# CH32X035C-R0.net
KiCad netlist of a schematic drawn in Altium Designer
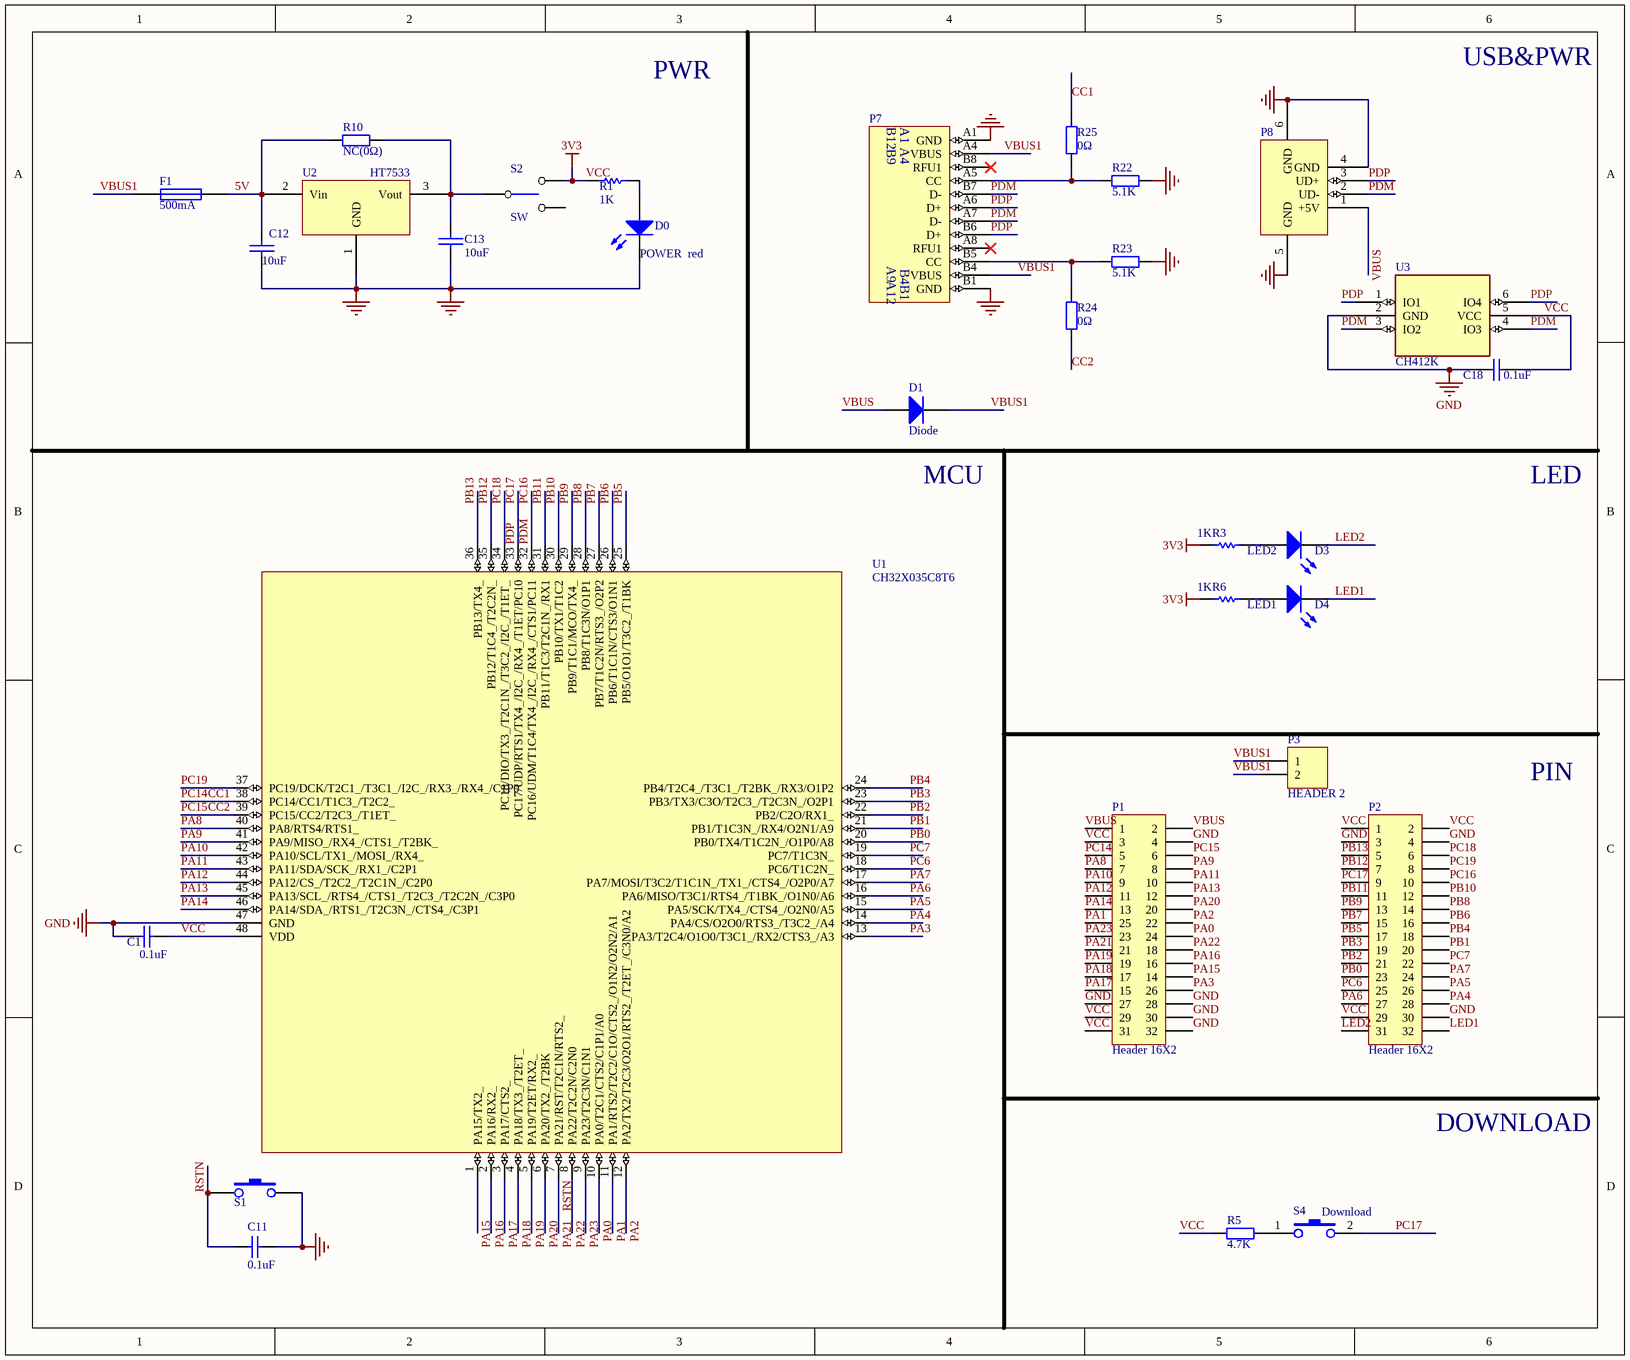
[diagram p0: CH32X035C-R0.SchDoc]

(export (version "E")
  (design (tool "Eeschema 10.0.6"))
  (components
    (comp (ref "C1")
      (value "0.1uF")
      (footprint "0603_C")
      (description "Capacitor")
      (libsource (lib "Miscellaneous Devices") (part "Cap"))
    )
    (comp (ref "C11")
      (value "0.1uF")
      (footprint "0603_C")
      (description "Capacitor")
      (libsource (lib "*") (part "Cap"))
    )
    (comp (ref "C12")
      (value "10uF")
      (footprint "0603_C")
      (description "Capacitor")
      (libsource (lib "*") (part "CAP"))
    )
    (comp (ref "C13")
      (value "10uF")
      (footprint "0603_C")
      (description "Capacitor")
      (libsource (lib "*") (part "CAP"))
    )
    (comp (ref "C18")
      (value "0.1uF")
      (footprint "0603_C")
      (description "Capacitor")
      (libsource (lib "Miscellaneous Devices") (part "Cap"))
    )
    (comp (ref "D0")
      (value "POWER  red")
      (footprint "0603+")
      (description "Typical INFRARED GaAs LED")
      (fields (field (name "PUBLISHER") "Altium Limited"))
      (libsource (lib "*") (part "LED0"))
    )
    (comp (ref "D1")
      (value "Diode")
      (footprint "SOD-123")
      (description "Default Diode")
      (fields (field (name "PUBLISHER") "Altium Limited"))
      (libsource (lib "Miscellaneous Devices") (part "Diode"))
    )
    (comp (ref "D3")
      (value "LED2")
      (footprint "0603+")
      (description "Typical INFRARED GaAs LED")
      (fields (field (name "PUBLISHER") "Altium Limited"))
      (libsource (lib "*") (part "LED0"))
    )
    (comp (ref "D4")
      (value "LED1")
      (footprint "0603+")
      (description "Typical INFRARED GaAs LED")
      (fields (field (name "PUBLISHER") "Altium Limited"))
      (libsource (lib "*") (part "LED0"))
    )
    (comp (ref "F1")
      (value "500mA")
      (footprint "0603")
      (description "Fuse")
      (libsource (lib "*") (part "FUSE1"))
    )
    (comp (ref "P1")
      (value "Header 16X2")
      (footprint "IDC32-2.54mm")
      (description "Header, 16-Pin, Dual row")
      (fields (field (name "PUBLISHER") "Altium Limited"))
      (libsource (lib "Miscellaneous Connectors") (part "Header 16X2"))
    )
    (comp (ref "P2")
      (value "Header 16X2")
      (footprint "IDC32-2.54mm")
      (description "Header, 16-Pin, Dual row")
      (fields (field (name "PUBLISHER") "Altium Limited"))
      (libsource (lib "") (part "Header 16X2_1"))
    )
    (comp (ref "P3")
      (value "HEADER 2")
      (footprint "SIP2-2.54mm")
      (description "Header, 2-Pin")
      (libsource (lib "wch_sch_others") (part "HEADER 2"))
    )
    (comp (ref "P7")
      (value "TYPE-C")
      (footprint "TYPE-C-Receptacle-2.0")
      (libsource (lib "*") (part "TYPE-C1"))
    )
    (comp (ref "P8")
      (value "USB_A")
      (footprint "USBAF")
      (description "USB Port")
      (libsource (lib "*") (part "USB"))
    )
    (comp (ref "R1")
      (value "1K")
      (footprint "0603")
      (description "Semiconductor Resistor")
      (libsource (lib "*") (part "Res Semi"))
    )
    (comp (ref "R3")
      (value "1K")
      (footprint "0603")
      (description "Semiconductor Resistor")
      (libsource (lib "*") (part "Res Semi"))
    )
    (comp (ref "R5")
      (value "4.7K")
      (footprint "0603")
      (description "Resistor")
      (libsource (lib "Miscellaneous Devices") (part "Res2"))
    )
    (comp (ref "R6")
      (value "1K")
      (footprint "0603")
      (description "Semiconductor Resistor")
      (libsource (lib "*") (part "Res Semi"))
    )
    (comp (ref "R10")
      (value "NC(0Ω)")
      (footprint "0603")
      (description "Resistor")
      (libsource (lib "*") (part "Res2"))
    )
    (comp (ref "R22")
      (value "5.1K")
      (footprint "0603")
      (description "Resistor")
      (libsource (lib "Miscellaneous Devices") (part "Res2"))
    )
    (comp (ref "R23")
      (value "5.1K")
      (footprint "0603")
      (description "Resistor")
      (libsource (lib "Miscellaneous Devices") (part "Res2"))
    )
    (comp (ref "R24")
      (value "0Ω")
      (footprint "0603")
      (description "Resistor")
      (libsource (lib "") (part "Res2_1"))
    )
    (comp (ref "R25")
      (value "0Ω")
      (footprint "0603")
      (description "Resistor")
      (libsource (lib "") (part "Res2_1"))
    )
    (comp (ref "S1") (value "KEY") (footprint "SMD_6.1x3.65x2.5mm-KEY") (libsource (lib "*") (part "KEY")))
    (comp (ref "S2") (value "SW") (footprint "SW1") (libsource (lib "*") (part "SW")))
    (comp (ref "S4")
      (value "Download")
      (footprint "SMD_6.1x3.65x2.5mm-KEY")
      (libsource (lib "wch_sch_others") (part "KEY1"))
    )
    (comp (ref "U1")
      (value "CH32X035C8T6")
      (footprint "LQFP48")
      (description "RISC-V MCU with USB/PD/ADC/SPI/I2C/UART/OA/CMP")
      (libsource (lib "CHXXX") (part "CH32X035C8T6"))
    )
    (comp (ref "U2")
      (value "HT7533")
      (footprint "SOT-89")
      (libsource (lib "wch_sch_others") (part "1117-3.3V"))
    )
    (comp (ref "U3")
      (value "CH412K")
      (footprint "SOT-363")
      (description "Qaud ESD protect, high speed")
      (libsource (lib "CHXXX") (part "CH412K"))
    )
  )
  (nets
    (net (code "1") (name "/5V") (class "Default")
      (node (ref "C12") (pin "1") (pinfunction "1_1") (pintype "passive"))
      (node (ref "F1") (pin "2") (pinfunction "2_2") (pintype "passive"))
      (node (ref "R10") (pin "2") (pinfunction "2_2") (pintype "passive"))
      (node (ref "U2") (pin "2") (pinfunction "Vin_2") (pintype "passive"))
    )
    (net (code "3") (name "/CC1") (class "Default")
      (node (ref "P1") (pin "5") (pinfunction "5_5") (pintype "passive"))
      (node (ref "R25") (pin "2") (pinfunction "2_2") (pintype "passive"))
      (node (ref "U1") (pin "38") (pinfunction "PC14/CC1/T1C3_/T2C2__38") (pintype "bidirectional"))
    )
    (net (code "4") (name "/CC2") (class "Default")
      (node (ref "P1") (pin "6") (pinfunction "6_6") (pintype "passive"))
      (node (ref "R24") (pin "1") (pinfunction "1_1") (pintype "passive"))
      (node (ref "U1") (pin "39") (pinfunction "PC15/CC2/T2C3_/T1ET__39") (pintype "bidirectional"))
    )
    (net (code "5") (name "/LED1") (class "Default")
      (node (ref "D4") (pin "2") (pinfunction "K_2") (pintype "passive"))
      (node (ref "P2") (pin "32") (pinfunction "32_32") (pintype "passive"))
    )
    (net (code "6") (name "/LED2") (class "Default")
      (node (ref "D3") (pin "2") (pinfunction "K_2") (pintype "passive"))
      (node (ref "P2") (pin "31") (pinfunction "31_31") (pintype "passive"))
    )
    (net (code "7") (name "/PA0") (class "Default")
      (node (ref "P1") (pin "24") (pinfunction "24_24") (pintype "passive"))
      (node (ref "U1") (pin "10") (pinfunction "PA0/T2C1/CTS2/C1P1/A0_10") (pintype "bidirectional"))
    )
    (net (code "8") (name "/PA1") (class "Default")
      (node (ref "P1") (pin "25") (pinfunction "25_25") (pintype "passive"))
      (node (ref "U1") (pin "11") (pinfunction "PA1/RTS2/T2C2/C1O/CTS2_/O1N2/O2N2/A1_11") (pintype "bidirectional"))
    )
    (net (code "9") (name "/PA2") (class "Default")
      (node (ref "P1") (pin "22") (pinfunction "22_22") (pintype "passive"))
      (node (ref "U1") (pin "12") (pinfunction "PA2/TX2/T2C3/O2O1/RTS2_/T2ET_/C3N0/A2_12") (pintype "bidirectional"))
    )
    (net (code "10") (name "/PA3") (class "Default")
      (node (ref "P1") (pin "26") (pinfunction "26_26") (pintype "passive"))
      (node (ref "U1") (pin "13") (pinfunction "PA3/T2C4/O1O0/T3C1_/RX2/CTS3_/A3_13") (pintype "bidirectional"))
    )
    (net (code "11") (name "/PA4") (class "Default")
      (node (ref "P2") (pin "28") (pinfunction "28_28") (pintype "passive"))
      (node (ref "U1") (pin "14") (pinfunction "PA4/CS/O2O0/RTS3_/T3C2_/A4_14") (pintype "bidirectional"))
    )
    (net (code "12") (name "/PA5") (class "Default")
      (node (ref "P2") (pin "26") (pinfunction "26_26") (pintype "passive"))
      (node (ref "U1") (pin "15") (pinfunction "PA5/SCK/TX4_/CTS4_/O2N0/A5_15") (pintype "bidirectional"))
    )
    (net (code "13") (name "/PA6") (class "Default")
      (node (ref "P2") (pin "27") (pinfunction "27_27") (pintype "passive"))
      (node (ref "U1") (pin "16") (pinfunction "PA6/MISO/T3C1/RTS4_/T1BK_/O1N0/A6_16") (pintype "bidirectional"))
    )
    (net (code "14") (name "/PA7") (class "Default")
      (node (ref "P2") (pin "24") (pinfunction "24_24") (pintype "passive"))
      (node (ref "U1") (pin "17") (pinfunction "PA7/MOSI/T3C2/T1C1N_/TX1_/CTS4_/O2P0/A7_17") (pintype "bidirectional"))
    )
    (net (code "15") (name "/PA8") (class "Default")
      (node (ref "P1") (pin "7") (pinfunction "7_7") (pintype "passive"))
      (node (ref "U1") (pin "40") (pinfunction "PA8/RTS4/RTS1__40") (pintype "bidirectional"))
    )
    (net (code "16") (name "/PA9") (class "Default")
      (node (ref "P1") (pin "8") (pinfunction "8_8") (pintype "passive"))
      (node (ref "U1") (pin "41") (pinfunction "PA9/MISO_/RX4_/CTS1_/T2BK__41") (pintype "bidirectional"))
    )
    (net (code "17") (name "/PA10") (class "Default")
      (node (ref "P1") (pin "9") (pinfunction "9_9") (pintype "passive"))
      (node (ref "U1") (pin "42") (pinfunction "PA10/SCL/TX1_/MOSI_/RX4__42") (pintype "bidirectional"))
    )
    (net (code "18") (name "/PA11") (class "Default")
      (node (ref "P1") (pin "10") (pinfunction "10_10") (pintype "passive"))
      (node (ref "U1") (pin "43") (pinfunction "PA11/SDA/SCK_/RX1_/C2P1_43") (pintype "bidirectional"))
    )
    (net (code "19") (name "/PA12") (class "Default")
      (node (ref "P1") (pin "11") (pinfunction "11_11") (pintype "passive"))
      (node (ref "U1") (pin "44") (pinfunction "PA12/CS_/T2C2_/T2C1N_/C2P0_44") (pintype "bidirectional"))
    )
    (net (code "20") (name "/PA13") (class "Default")
      (node (ref "P1") (pin "12") (pinfunction "12_12") (pintype "passive"))
      (node (ref "U1") (pin "45") (pinfunction "PA13/SCL_/RTS4_/CTS1_/T2C3_/T2C2N_/C3P0_45") (pintype "bidirectional"))
    )
    (net (code "21") (name "/PA14") (class "Default")
      (node (ref "P1") (pin "13") (pinfunction "13_13") (pintype "passive"))
      (node (ref "U1") (pin "46") (pinfunction "PA14/SDA_/RTS1_/T2C3N_/CTS4_/C3P1_46") (pintype "bidirectional"))
    )
    (net (code "22") (name "/PA15") (class "Default")
      (node (ref "P1") (pin "14") (pinfunction "14_14") (pintype "passive"))
      (node (ref "U1") (pin "1") (pinfunction "PA15/TX2__1") (pintype "bidirectional"))
    )
    (net (code "23") (name "/PA16") (class "Default")
      (node (ref "P1") (pin "16") (pinfunction "16_16") (pintype "passive"))
      (node (ref "U1") (pin "2") (pinfunction "PA16/RX2__2") (pintype "bidirectional"))
    )
    (net (code "24") (name "/PA17") (class "Default")
      (node (ref "P1") (pin "15") (pinfunction "15_15") (pintype "passive"))
      (node (ref "U1") (pin "3") (pinfunction "PA17/CTS2__3") (pintype "bidirectional"))
    )
    (net (code "25") (name "/PA18") (class "Default")
      (node (ref "P1") (pin "17") (pinfunction "17_17") (pintype "passive"))
      (node (ref "U1") (pin "4") (pinfunction "PA18/TX3_/T2ET__4") (pintype "bidirectional"))
    )
    (net (code "26") (name "/PA19") (class "Default")
      (node (ref "P1") (pin "19") (pinfunction "19_19") (pintype "passive"))
      (node (ref "U1") (pin "5") (pinfunction "PA19/T2ET/RX2__5") (pintype "bidirectional"))
    )
    (net (code "27") (name "/PA20") (class "Default")
      (node (ref "P1") (pin "20") (pinfunction "20_20") (pintype "passive"))
      (node (ref "U1") (pin "6") (pinfunction "PA20/TX2_/T2BK_6") (pintype "bidirectional"))
    )
    (net (code "28") (name "/PA21") (class "Default")
      (node (ref "C11") (pin "2") (pinfunction "2_2") (pintype "passive"))
      (node (ref "P1") (pin "21") (pinfunction "21_21") (pintype "passive"))
      (node (ref "S1") (pin "1") (pinfunction "1_1") (pintype "passive"))
      (node (ref "U1") (pin "7") (pinfunction "PA21/RST/T2C1N/RTS2__7") (pintype "bidirectional"))
    )
    (net (code "29") (name "/PA22") (class "Default")
      (node (ref "P1") (pin "18") (pinfunction "18_18") (pintype "passive"))
      (node (ref "U1") (pin "8") (pinfunction "PA22/T2C2N/C2N0_8") (pintype "bidirectional"))
    )
    (net (code "30") (name "/PA23") (class "Default")
      (node (ref "P1") (pin "23") (pinfunction "23_23") (pintype "passive"))
      (node (ref "U1") (pin "9") (pinfunction "PA23/T2C3N/C1N1_9") (pintype "bidirectional"))
    )
    (net (code "31") (name "/PB0") (class "Default")
      (node (ref "P2") (pin "23") (pinfunction "23_23") (pintype "passive"))
      (node (ref "U1") (pin "20") (pinfunction "PB0/TX4/T1C2N_/O1P0/A8_20") (pintype "bidirectional"))
    )
    (net (code "32") (name "/PB1") (class "Default")
      (node (ref "P2") (pin "20") (pinfunction "20_20") (pintype "passive"))
      (node (ref "U1") (pin "21") (pinfunction "PB1/T1C3N_/RX4/O2N1/A9_21") (pintype "bidirectional"))
    )
    (net (code "33") (name "/PB2") (class "Default")
      (node (ref "P2") (pin "21") (pinfunction "21_21") (pintype "passive"))
      (node (ref "U1") (pin "22") (pinfunction "PB2/C2O/RX1__22") (pintype "bidirectional"))
    )
    (net (code "34") (name "/PB3") (class "Default")
      (node (ref "P2") (pin "19") (pinfunction "19_19") (pintype "passive"))
      (node (ref "U1") (pin "23") (pinfunction "PB3/TX3/C3O/T2C3_/T2C3N_/O2P1_23") (pintype "bidirectional"))
    )
    (net (code "35") (name "/PB4") (class "Default")
      (node (ref "P2") (pin "18") (pinfunction "18_18") (pintype "passive"))
      (node (ref "U1") (pin "24") (pinfunction "PB4/T2C4_/T3C1_/T2BK_/RX3/O1P2_24") (pintype "bidirectional"))
    )
    (net (code "36") (name "/PB5") (class "Default")
      (node (ref "P2") (pin "17") (pinfunction "17_17") (pintype "passive"))
      (node (ref "U1") (pin "25") (pinfunction "PB5/O1O1/T3C2_/T1BK_25") (pintype "bidirectional"))
    )
    (net (code "37") (name "/PB6") (class "Default")
      (node (ref "P2") (pin "16") (pinfunction "16_16") (pintype "passive"))
      (node (ref "U1") (pin "26") (pinfunction "PB6/T1C1N/CTS3/O1N1_26") (pintype "bidirectional"))
    )
    (net (code "38") (name "/PB7") (class "Default")
      (node (ref "P2") (pin "15") (pinfunction "15_15") (pintype "passive"))
      (node (ref "U1") (pin "27") (pinfunction "PB7/T1C2N/RTS3_/O2P2_27") (pintype "bidirectional"))
    )
    (net (code "39") (name "/PB8") (class "Default")
      (node (ref "P2") (pin "14") (pinfunction "14_14") (pintype "passive"))
      (node (ref "U1") (pin "28") (pinfunction "PB8/T1C3N/O1P1_28") (pintype "bidirectional"))
    )
    (net (code "40") (name "/PB9") (class "Default")
      (node (ref "P2") (pin "13") (pinfunction "13_13") (pintype "passive"))
      (node (ref "U1") (pin "29") (pinfunction "PB9/T1C1/MCO/TX4__29") (pintype "bidirectional"))
    )
    (net (code "41") (name "/PB10") (class "Default")
      (node (ref "P2") (pin "12") (pinfunction "12_12") (pintype "passive"))
      (node (ref "U1") (pin "30") (pinfunction "PB10/TX1/T1C2_30") (pintype "bidirectional"))
    )
    (net (code "42") (name "/PB11") (class "Default")
      (node (ref "P2") (pin "11") (pinfunction "11_11") (pintype "passive"))
      (node (ref "U1") (pin "31") (pinfunction "PB11/T1C3/T2C1N_/RX1_31") (pintype "bidirectional"))
    )
    (net (code "43") (name "/PB12") (class "Default")
      (node (ref "P2") (pin "7") (pinfunction "7_7") (pintype "passive"))
      (node (ref "U1") (pin "35") (pinfunction "PB12/T1C4_/T2C2N__35") (pintype "bidirectional"))
    )
    (net (code "44") (name "/PB13") (class "Default")
      (node (ref "P2") (pin "5") (pinfunction "5_5") (pintype "passive"))
      (node (ref "U1") (pin "36") (pinfunction "PB13/TX4__36") (pintype "bidirectional"))
    )
    (net (code "45") (name "/PC6") (class "Default")
      (node (ref "P2") (pin "25") (pinfunction "25_25") (pintype "passive"))
      (node (ref "U1") (pin "18") (pinfunction "PC6/T1C2N__18") (pintype "bidirectional"))
    )
    (net (code "46") (name "/PC7") (class "Default")
      (node (ref "P2") (pin "22") (pinfunction "22_22") (pintype "passive"))
      (node (ref "U1") (pin "19") (pinfunction "PC7/T1C3N__19") (pintype "bidirectional"))
    )
    (net (code "47") (name "/PC16") (class "Default")
      (node (ref "P2") (pin "10") (pinfunction "10_10") (pintype "passive"))
      (node (ref "P7") (pin "A7") (pinfunction "D-_A7") (pintype "bidirectional"))
      (node (ref "P7") (pin "B7") (pinfunction "D-_B7") (pintype "bidirectional"))
      (node (ref "P8") (pin "2") (pinfunction "UD-_2") (pintype "bidirectional"))
      (node (ref "U1") (pin "32") (pinfunction "PC16/UDM/T1C4/TX4_/I2C_/RX4_/CTS1/PC11_32") (pintype "bidirectional"))
      (node (ref "U3") (pin "3") (pinfunction "IO2_3") (pintype "bidirectional"))
      (node (ref "U3") (pin "4") (pinfunction "IO3_4") (pintype "bidirectional"))
    )
    (net (code "48") (name "/PC17") (class "Default")
      (node (ref "P2") (pin "9") (pinfunction "9_9") (pintype "passive"))
      (node (ref "P7") (pin "A6") (pinfunction "D+_A6") (pintype "bidirectional"))
      (node (ref "P7") (pin "B6") (pinfunction "D+_B6") (pintype "bidirectional"))
      (node (ref "P8") (pin "3") (pinfunction "UD+_3") (pintype "bidirectional"))
      (node (ref "S4") (pin "2") (pinfunction "2_2") (pintype "passive"))
      (node (ref "U1") (pin "33") (pinfunction "PC17/UDP/RTS1/TX4_/I2C_/RX4_/T1ET/PC10_33") (pintype "bidirectional"))
      (node (ref "U3") (pin "1") (pinfunction "IO1_1") (pintype "bidirectional"))
      (node (ref "U3") (pin "6") (pinfunction "IO4_6") (pintype "bidirectional"))
    )
    (net (code "49") (name "/PC18") (class "Default")
      (node (ref "P2") (pin "6") (pinfunction "6_6") (pintype "passive"))
      (node (ref "U1") (pin "34") (pinfunction "PC18/DIO/TX3_/T2C1N_/T3C2_/I2C_/T1ET__34") (pintype "bidirectional"))
    )
    (net (code "50") (name "/PC19") (class "Default")
      (node (ref "P2") (pin "8") (pinfunction "8_8") (pintype "passive"))
      (node (ref "U1") (pin "37") (pinfunction "PC19/DCK/T2C1_/T3C1_/I2C_/RX3_/RX4_/C1P0_37") (pintype "bidirectional"))
    )
    (net (code "51") (name "/VBUS") (class "Default")
      (node (ref "D1") (pin "1") (pinfunction "A_1") (pintype "passive"))
      (node (ref "P1") (pin "1") (pinfunction "1_1") (pintype "passive"))
      (node (ref "P1") (pin "2") (pinfunction "2_2") (pintype "passive"))
      (node (ref "P8") (pin "1") (pinfunction "+5V_1") (pintype "power_in"))
    )
    (net (code "52") (name "/VBUS1") (class "Default")
      (node (ref "D1") (pin "2") (pinfunction "K_2") (pintype "passive"))
      (node (ref "F1") (pin "1") (pinfunction "1_1") (pintype "passive"))
      (node (ref "P3") (pin "1") (pinfunction "1_1") (pintype "passive"))
      (node (ref "P3") (pin "2") (pinfunction "2_2") (pintype "passive"))
      (node (ref "P7") (pin "A4") (pinfunction "VBUS_A4") (pintype "bidirectional"))
      (node (ref "P7") (pin "B4") (pinfunction "VBUS_B4") (pintype "bidirectional"))
    )
    (net (code "53") (name "3V3") (class "Default")
      (node (ref "C1") (pin "2") (pinfunction "2_2") (pintype "passive"))
      (node (ref "C18") (pin "2") (pinfunction "2_2") (pintype "passive"))
      (node (ref "P1") (pin "29") (pinfunction "29_29") (pintype "passive"))
      (node (ref "P1") (pin "3") (pinfunction "3_3") (pintype "passive"))
      (node (ref "P1") (pin "31") (pinfunction "31_31") (pintype "passive"))
      (node (ref "P2") (pin "1") (pinfunction "1_1") (pintype "passive"))
      (node (ref "P2") (pin "2") (pinfunction "2_2") (pintype "passive"))
      (node (ref "P2") (pin "29") (pinfunction "29_29") (pintype "passive"))
      (node (ref "R1") (pin "2") (pinfunction "2_2") (pintype "passive"))
      (node (ref "R3") (pin "1") (pinfunction "1_1") (pintype "passive"))
      (node (ref "R5") (pin "1") (pinfunction "1_1") (pintype "passive"))
      (node (ref "R6") (pin "1") (pinfunction "1_1") (pintype "passive"))
      (node (ref "S2") (pin "3") (pinfunction "3_3") (pintype "passive"))
      (node (ref "U1") (pin "48") (pinfunction "VDD_48") (pintype "power_in"))
      (node (ref "U3") (pin "5") (pinfunction "VCC_5") (pintype "power_in"))
    )
    (net (code "54") (name "GND") (class "Default")
      (node (ref "C1") (pin "1") (pinfunction "1_1") (pintype "passive"))
      (node (ref "C11") (pin "1") (pinfunction "1_1") (pintype "passive"))
      (node (ref "C12") (pin "2") (pinfunction "2_2") (pintype "passive"))
      (node (ref "C13") (pin "2") (pinfunction "2_2") (pintype "passive"))
      (node (ref "C18") (pin "1") (pinfunction "1_1") (pintype "passive"))
      (node (ref "D0") (pin "2") (pinfunction "K_2") (pintype "passive"))
      (node (ref "P1") (pin "27") (pinfunction "27_27") (pintype "passive"))
      (node (ref "P1") (pin "28") (pinfunction "28_28") (pintype "passive"))
      (node (ref "P1") (pin "30") (pinfunction "30_30") (pintype "passive"))
      (node (ref "P1") (pin "32") (pinfunction "32_32") (pintype "passive"))
      (node (ref "P1") (pin "4") (pinfunction "4_4") (pintype "passive"))
      (node (ref "P2") (pin "3") (pinfunction "3_3") (pintype "passive"))
      (node (ref "P2") (pin "30") (pinfunction "30_30") (pintype "passive"))
      (node (ref "P2") (pin "4") (pinfunction "4_4") (pintype "passive"))
      (node (ref "P7") (pin "A1") (pinfunction "GND_A1") (pintype "bidirectional"))
      (node (ref "P7") (pin "B1") (pinfunction "GND_B1") (pintype "bidirectional"))
      (node (ref "P8") (pin "4") (pinfunction "GND_4") (pintype "power_in"))
      (node (ref "P8") (pin "5") (pinfunction "GND_5") (pintype "power_in"))
      (node (ref "P8") (pin "6") (pinfunction "GND_6") (pintype "power_in"))
      (node (ref "R22") (pin "2") (pinfunction "2_2") (pintype "passive"))
      (node (ref "R23") (pin "2") (pinfunction "2_2") (pintype "passive"))
      (node (ref "S1") (pin "2") (pinfunction "2_2") (pintype "passive"))
      (node (ref "U1") (pin "47") (pinfunction "GND_47") (pintype "power_in"))
      (node (ref "U2") (pin "1") (pinfunction "GND_1") (pintype "passive"))
      (node (ref "U3") (pin "2") (pinfunction "GND_2") (pintype "power_in"))
    )
    (net (code "55") (name "Net-(D0-A)") (class "Default")
      (node (ref "D0") (pin "1") (pinfunction "A_1") (pintype "passive"))
      (node (ref "R1") (pin "1") (pinfunction "1_1") (pintype "passive"))
    )
    (net (code "56") (name "Net-(D3-A)") (class "Default")
      (node (ref "D3") (pin "1") (pinfunction "A_1") (pintype "passive"))
      (node (ref "R3") (pin "2") (pinfunction "2_2") (pintype "passive"))
    )
    (net (code "57") (name "Net-(D4-A)") (class "Default")
      (node (ref "D4") (pin "1") (pinfunction "A_1") (pintype "passive"))
      (node (ref "R6") (pin "2") (pinfunction "2_2") (pintype "passive"))
    )
    (net (code "58") (name "Net-(P7-CC-PadA5)") (class "Default")
      (node (ref "P7") (pin "A5") (pinfunction "CC_A5") (pintype "bidirectional"))
      (node (ref "R22") (pin "1") (pinfunction "1_1") (pintype "passive"))
      (node (ref "R25") (pin "1") (pinfunction "1_1") (pintype "passive"))
    )
    (net (code "59") (name "Net-(P7-CC-PadB5)") (class "Default")
      (node (ref "P7") (pin "B5") (pinfunction "CC_B5") (pintype "bidirectional"))
      (node (ref "R23") (pin "1") (pinfunction "1_1") (pintype "passive"))
      (node (ref "R24") (pin "2") (pinfunction "2_2") (pintype "passive"))
    )
    (net (code "60") (name "Net-(R5-Pad2)") (class "Default")
      (node (ref "R5") (pin "2") (pinfunction "2_2") (pintype "passive"))
      (node (ref "S4") (pin "1") (pinfunction "1_1") (pintype "passive"))
    )
    (net (code "61") (name "Net-(U2-Vout)") (class "Default")
      (node (ref "C13") (pin "1") (pinfunction "1_1") (pintype "passive"))
      (node (ref "R10") (pin "1") (pinfunction "1_1") (pintype "passive"))
      (node (ref "S2") (pin "1") (pinfunction "1_1") (pintype "passive"))
      (node (ref "U2") (pin "3") (pinfunction "Vout_3") (pintype "passive"))
    )
    (net (code "62") (name "unconnected-(P7-RFU1-PadA8)") (class "Default")
      (node (ref "P7") (pin "A8") (pinfunction "RFU1_A8") (pintype "bidirectional+no_connect"))
    )
    (net (code "63") (name "unconnected-(P7-RFU1-PadB8)") (class "Default")
      (node (ref "P7") (pin "B8") (pinfunction "RFU1_B8") (pintype "bidirectional+no_connect"))
    )
    (net (code "64") (name "unconnected-(S2-Pad2)") (class "Default")
      (node (ref "S2") (pin "2") (pinfunction "2_2") (pintype "passive"))
    )
  )
)
